# 4OR_1.net
KiCad netlist of a schematic drawn in EAGLE
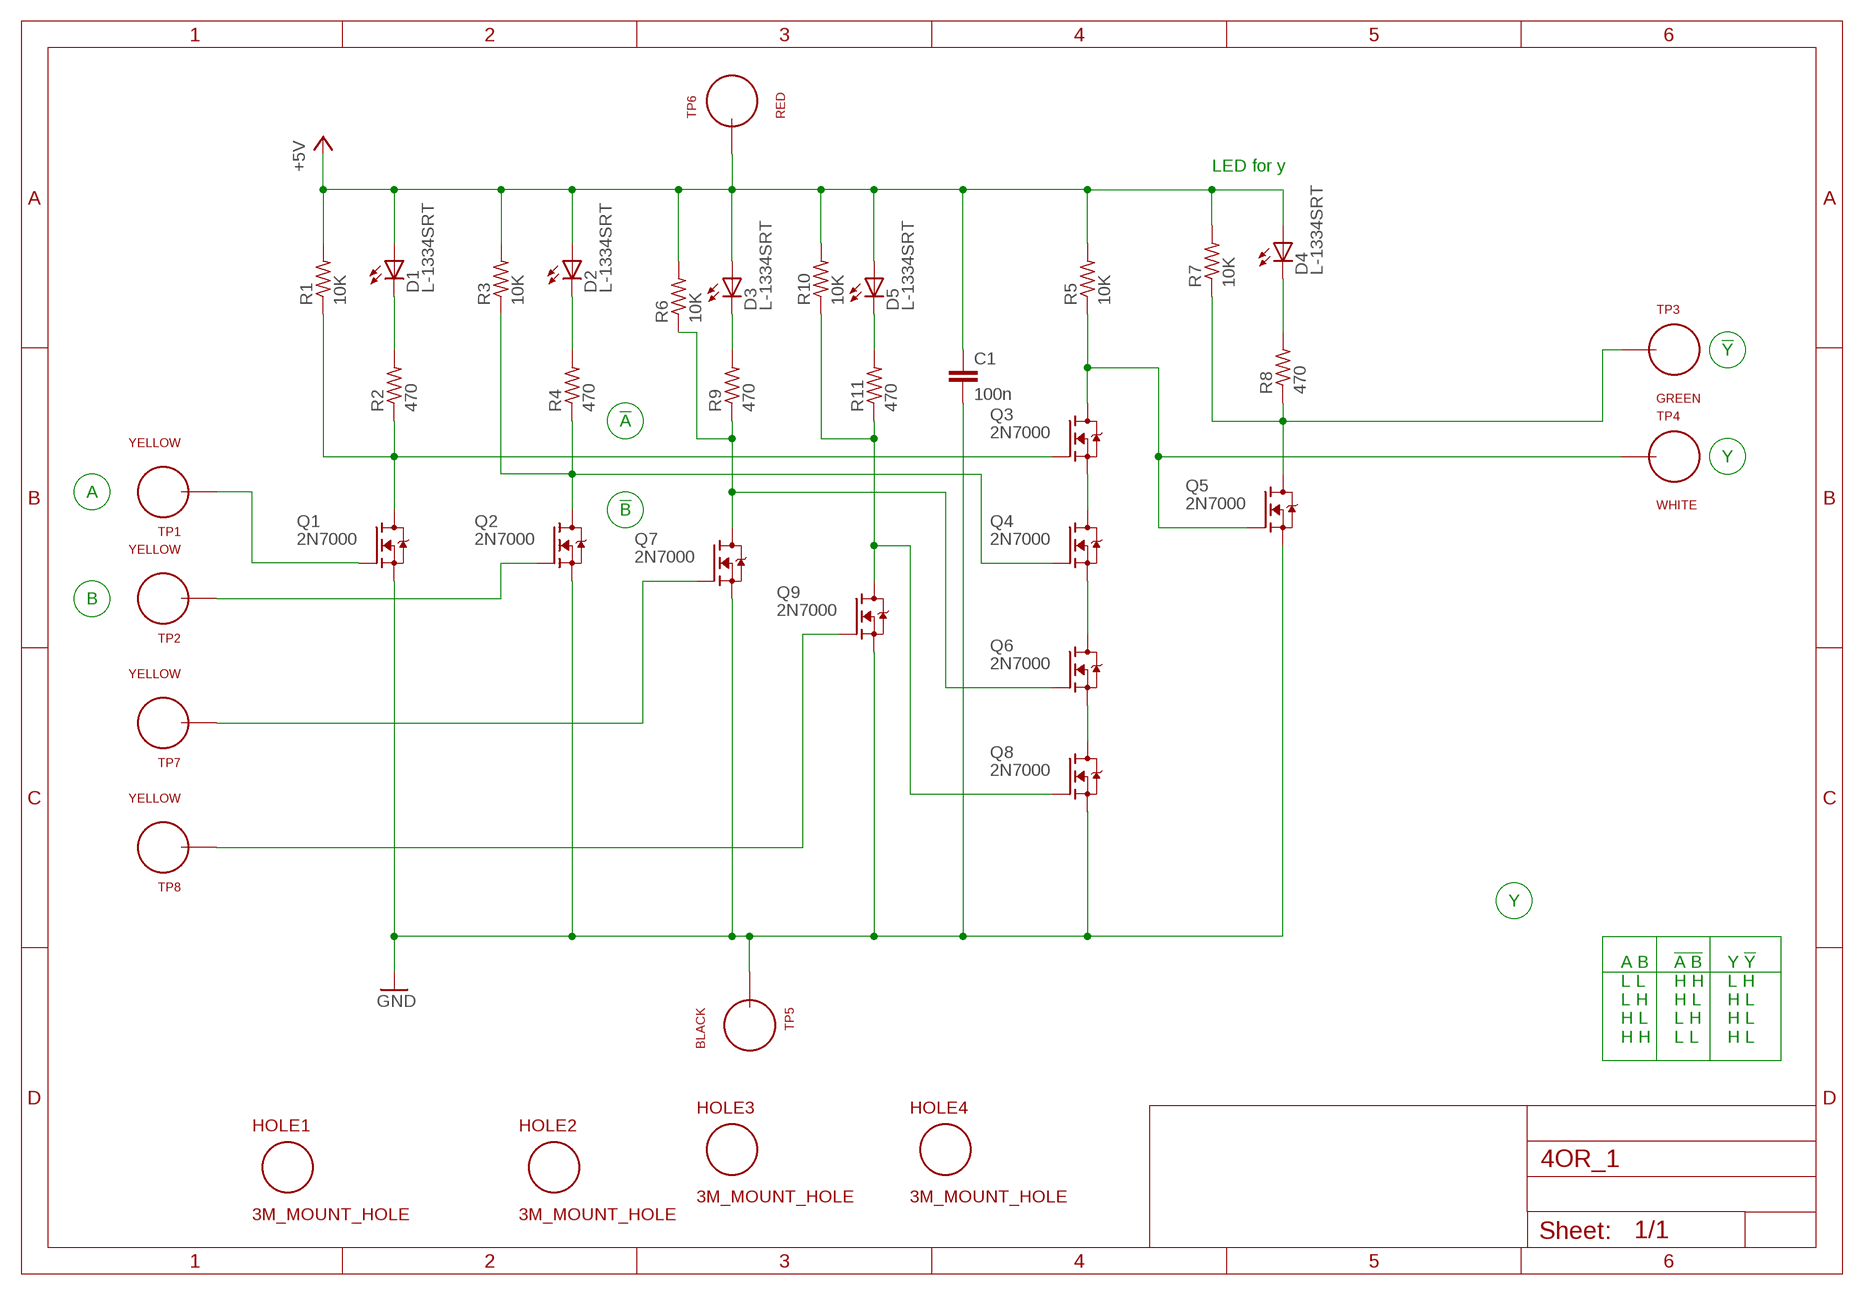
[diagram p0: schematic, sheet 1]

(export (version "E")
  (design (tool "Eeschema 10.0.6"))
  (components
    (comp (ref "C1")
      (value "100n")
      (footprint "eagle-import:CAP_P2INCH")
      (libsource (lib "eagle-import") (part "C_P2INCH"))
    )
    (comp (ref "D1")
      (value "L-1334SRT")
      (footprint "eagle-import:LED3MM")
      (libsource (lib "eagle-import") (part "L-1334SRT"))
    )
    (comp (ref "D2")
      (value "L-1334SRT")
      (footprint "eagle-import:LED3MM")
      (libsource (lib "eagle-import") (part "L-1334SRT"))
    )
    (comp (ref "D3")
      (value "L-1334SRT")
      (footprint "eagle-import:LED3MM")
      (libsource (lib "eagle-import") (part "L-1334SRT"))
    )
    (comp (ref "D4")
      (value "L-1334SRT")
      (footprint "eagle-import:LED3MM")
      (libsource (lib "eagle-import") (part "L-1334SRT"))
    )
    (comp (ref "D5")
      (value "L-1334SRT")
      (footprint "eagle-import:LED3MM")
      (libsource (lib "eagle-import") (part "L-1334SRT"))
    )
    (comp (ref "HOLE1")
      (value "3M_MOUNT_HOLE")
      (footprint "eagle-import:3M_HOLE")
      (libsource (lib "eagle-import") (part "3M_MOUNT_HOLE"))
    )
    (comp (ref "HOLE2")
      (value "3M_MOUNT_HOLE")
      (footprint "eagle-import:3M_HOLE")
      (libsource (lib "eagle-import") (part "3M_MOUNT_HOLE"))
    )
    (comp (ref "HOLE3")
      (value "3M_MOUNT_HOLE")
      (footprint "eagle-import:3M_HOLE")
      (libsource (lib "eagle-import") (part "3M_MOUNT_HOLE"))
    )
    (comp (ref "HOLE4")
      (value "3M_MOUNT_HOLE")
      (footprint "eagle-import:3M_HOLE")
      (libsource (lib "eagle-import") (part "3M_MOUNT_HOLE"))
    )
    (comp (ref "Q1")
      (value "2N7000")
      (footprint "eagle-import:TO92-DGS")
      (libsource (lib "eagle-import") (part "2N7000"))
    )
    (comp (ref "Q2")
      (value "2N7000")
      (footprint "eagle-import:TO92-DGS")
      (libsource (lib "eagle-import") (part "2N7000"))
    )
    (comp (ref "Q3")
      (value "2N7000")
      (footprint "eagle-import:TO92-DGS")
      (libsource (lib "eagle-import") (part "2N7000"))
    )
    (comp (ref "Q4")
      (value "2N7000")
      (footprint "eagle-import:TO92-DGS")
      (libsource (lib "eagle-import") (part "2N7000"))
    )
    (comp (ref "Q5")
      (value "2N7000")
      (footprint "eagle-import:TO92-DGS")
      (libsource (lib "eagle-import") (part "2N7000"))
    )
    (comp (ref "Q6")
      (value "2N7000")
      (footprint "eagle-import:TO92-DGS")
      (libsource (lib "eagle-import") (part "2N7000"))
    )
    (comp (ref "Q7")
      (value "2N7000")
      (footprint "eagle-import:TO92-DGS")
      (libsource (lib "eagle-import") (part "2N7000"))
    )
    (comp (ref "Q8")
      (value "2N7000")
      (footprint "eagle-import:TO92-DGS")
      (libsource (lib "eagle-import") (part "2N7000"))
    )
    (comp (ref "Q9")
      (value "2N7000")
      (footprint "eagle-import:TO92-DGS")
      (libsource (lib "eagle-import") (part "2N7000"))
    )
    (comp (ref "R1")
      (value "10K")
      (footprint "eagle-import:R_P2INCH")
      (libsource (lib "eagle-import") (part "R_P2INCH"))
    )
    (comp (ref "R2")
      (value "470")
      (footprint "eagle-import:R_P2INCH")
      (libsource (lib "eagle-import") (part "R_P2INCH"))
    )
    (comp (ref "R3")
      (value "10K")
      (footprint "eagle-import:R_P2INCH")
      (libsource (lib "eagle-import") (part "R_P2INCH"))
    )
    (comp (ref "R4")
      (value "470")
      (footprint "eagle-import:R_P2INCH")
      (libsource (lib "eagle-import") (part "R_P2INCH"))
    )
    (comp (ref "R5")
      (value "10K")
      (footprint "eagle-import:R_P2INCH")
      (libsource (lib "eagle-import") (part "R_P2INCH"))
    )
    (comp (ref "R6")
      (value "10K")
      (footprint "eagle-import:R_P2INCH")
      (libsource (lib "eagle-import") (part "R_P2INCH"))
    )
    (comp (ref "R7")
      (value "10K")
      (footprint "eagle-import:R_P2INCH")
      (libsource (lib "eagle-import") (part "R_P2INCH"))
    )
    (comp (ref "R8")
      (value "470")
      (footprint "eagle-import:R_P2INCH")
      (libsource (lib "eagle-import") (part "R_P2INCH"))
    )
    (comp (ref "R9")
      (value "470")
      (footprint "eagle-import:R_P2INCH")
      (libsource (lib "eagle-import") (part "R_P2INCH"))
    )
    (comp (ref "R10")
      (value "10K")
      (footprint "eagle-import:R_P2INCH")
      (libsource (lib "eagle-import") (part "R_P2INCH"))
    )
    (comp (ref "R11")
      (value "470")
      (footprint "eagle-import:R_P2INCH")
      (libsource (lib "eagle-import") (part "R_P2INCH"))
    )
    (comp (ref "TP1")
      (value "YELLOW")
      (footprint "eagle-import:TEST_LOOP")
      (libsource (lib "eagle-import") (part "TEST_LOOP"))
    )
    (comp (ref "TP2")
      (value "YELLOW")
      (footprint "eagle-import:TEST_LOOP")
      (libsource (lib "eagle-import") (part "TEST_LOOP"))
    )
    (comp (ref "TP3")
      (value "GREEN")
      (footprint "eagle-import:TEST_LOOP")
      (libsource (lib "eagle-import") (part "TEST_LOOP"))
    )
    (comp (ref "TP4")
      (value "WHITE")
      (footprint "eagle-import:TEST_LOOP")
      (libsource (lib "eagle-import") (part "TEST_LOOP"))
    )
    (comp (ref "TP5")
      (value "BLACK")
      (footprint "eagle-import:TEST_LOOP")
      (libsource (lib "eagle-import") (part "TEST_LOOP"))
    )
    (comp (ref "TP6")
      (value "RED")
      (footprint "eagle-import:TEST_LOOP")
      (libsource (lib "eagle-import") (part "TEST_LOOP"))
    )
    (comp (ref "TP7")
      (value "YELLOW")
      (footprint "eagle-import:TEST_LOOP")
      (libsource (lib "eagle-import") (part "TEST_LOOP"))
    )
    (comp (ref "TP8")
      (value "YELLOW")
      (footprint "eagle-import:TEST_LOOP")
      (libsource (lib "eagle-import") (part "TEST_LOOP"))
    )
  )
  (nets
    (net (code "1") (name "+5V") (class "Default")
      (node (ref "C1") (pin "1") (pinfunction "1_1") (pintype "passive"))
      (node (ref "D1") (pin "A") (pinfunction "A_A") (pintype "passive"))
      (node (ref "D2") (pin "A") (pinfunction "A_A") (pintype "passive"))
      (node (ref "D3") (pin "A") (pinfunction "A_A") (pintype "passive"))
      (node (ref "D4") (pin "A") (pinfunction "A_A") (pintype "passive"))
      (node (ref "D5") (pin "A") (pinfunction "A_A") (pintype "passive"))
      (node (ref "R1") (pin "2") (pinfunction "2_2") (pintype "passive"))
      (node (ref "R10") (pin "2") (pinfunction "2_2") (pintype "passive"))
      (node (ref "R3") (pin "2") (pinfunction "2_2") (pintype "passive"))
      (node (ref "R5") (pin "2") (pinfunction "2_2") (pintype "passive"))
      (node (ref "R6") (pin "2") (pinfunction "2_2") (pintype "passive"))
      (node (ref "R7") (pin "2") (pinfunction "2_2") (pintype "passive"))
      (node (ref "TP6") (pin "P$1") (pinfunction "P$1_P$1") (pintype "bidirectional"))
    )
    (net (code "2") (name "GND") (class "Default")
      (node (ref "C1") (pin "2") (pinfunction "2_2") (pintype "passive"))
      (node (ref "Q1") (pin "S") (pinfunction "S_S") (pintype "passive"))
      (node (ref "Q2") (pin "S") (pinfunction "S_S") (pintype "passive"))
      (node (ref "Q5") (pin "S") (pinfunction "S_S") (pintype "passive"))
      (node (ref "Q7") (pin "S") (pinfunction "S_S") (pintype "passive"))
      (node (ref "Q8") (pin "S") (pinfunction "S_S") (pintype "passive"))
      (node (ref "Q9") (pin "S") (pinfunction "S_S") (pintype "passive"))
      (node (ref "TP5") (pin "P$1") (pinfunction "P$1_P$1") (pintype "bidirectional"))
    )
    (net (code "3") (name "Net-(D1-C)") (class "Default")
      (node (ref "D1") (pin "K") (pinfunction "C_K") (pintype "passive"))
      (node (ref "R2") (pin "2") (pinfunction "2_2") (pintype "passive"))
    )
    (net (code "4") (name "Net-(D2-C)") (class "Default")
      (node (ref "D2") (pin "K") (pinfunction "C_K") (pintype "passive"))
      (node (ref "R4") (pin "2") (pinfunction "2_2") (pintype "passive"))
    )
    (net (code "5") (name "Net-(D3-C)") (class "Default")
      (node (ref "D3") (pin "K") (pinfunction "C_K") (pintype "passive"))
      (node (ref "R9") (pin "2") (pinfunction "2_2") (pintype "passive"))
    )
    (net (code "6") (name "Net-(D4-C)") (class "Default")
      (node (ref "D4") (pin "K") (pinfunction "C_K") (pintype "passive"))
      (node (ref "R8") (pin "2") (pinfunction "2_2") (pintype "passive"))
    )
    (net (code "7") (name "Net-(D5-C)") (class "Default")
      (node (ref "D5") (pin "K") (pinfunction "C_K") (pintype "passive"))
      (node (ref "R11") (pin "2") (pinfunction "2_2") (pintype "passive"))
    )
    (net (code "8") (name "Net-(Q1-PadD)") (class "Default")
      (node (ref "Q1") (pin "D") (pinfunction "D_D") (pintype "passive"))
      (node (ref "Q3") (pin "G") (pinfunction "G_G") (pintype "passive"))
      (node (ref "R1") (pin "1") (pinfunction "1_1") (pintype "passive"))
      (node (ref "R2") (pin "1") (pinfunction "1_1") (pintype "passive"))
    )
    (net (code "9") (name "Net-(Q1-PadG)") (class "Default")
      (node (ref "Q1") (pin "G") (pinfunction "G_G") (pintype "passive"))
      (node (ref "TP1") (pin "P$1") (pinfunction "P$1_P$1") (pintype "bidirectional"))
    )
    (net (code "10") (name "Net-(Q2-PadD)") (class "Default")
      (node (ref "Q2") (pin "D") (pinfunction "D_D") (pintype "passive"))
      (node (ref "Q4") (pin "G") (pinfunction "G_G") (pintype "passive"))
      (node (ref "R3") (pin "1") (pinfunction "1_1") (pintype "passive"))
      (node (ref "R4") (pin "1") (pinfunction "1_1") (pintype "passive"))
    )
    (net (code "11") (name "Net-(Q2-PadG)") (class "Default")
      (node (ref "Q2") (pin "G") (pinfunction "G_G") (pintype "passive"))
      (node (ref "TP2") (pin "P$1") (pinfunction "P$1_P$1") (pintype "bidirectional"))
    )
    (net (code "12") (name "Net-(Q3-PadD)") (class "Default")
      (node (ref "Q3") (pin "D") (pinfunction "D_D") (pintype "passive"))
      (node (ref "Q5") (pin "G") (pinfunction "G_G") (pintype "passive"))
      (node (ref "R5") (pin "1") (pinfunction "1_1") (pintype "passive"))
      (node (ref "TP4") (pin "P$1") (pinfunction "P$1_P$1") (pintype "bidirectional"))
    )
    (net (code "13") (name "Net-(Q3-PadS)") (class "Default")
      (node (ref "Q3") (pin "S") (pinfunction "S_S") (pintype "passive"))
      (node (ref "Q4") (pin "D") (pinfunction "D_D") (pintype "passive"))
    )
    (net (code "14") (name "Net-(Q4-PadS)") (class "Default")
      (node (ref "Q4") (pin "S") (pinfunction "S_S") (pintype "passive"))
      (node (ref "Q6") (pin "D") (pinfunction "D_D") (pintype "passive"))
    )
    (net (code "15") (name "Net-(Q5-PadD)") (class "Default")
      (node (ref "Q5") (pin "D") (pinfunction "D_D") (pintype "passive"))
      (node (ref "R7") (pin "1") (pinfunction "1_1") (pintype "passive"))
      (node (ref "R8") (pin "1") (pinfunction "1_1") (pintype "passive"))
      (node (ref "TP3") (pin "P$1") (pinfunction "P$1_P$1") (pintype "bidirectional"))
    )
    (net (code "16") (name "Net-(Q6-PadG)") (class "Default")
      (node (ref "Q6") (pin "G") (pinfunction "G_G") (pintype "passive"))
      (node (ref "Q7") (pin "D") (pinfunction "D_D") (pintype "passive"))
      (node (ref "R6") (pin "1") (pinfunction "1_1") (pintype "passive"))
      (node (ref "R9") (pin "1") (pinfunction "1_1") (pintype "passive"))
    )
    (net (code "17") (name "Net-(Q6-PadS)") (class "Default")
      (node (ref "Q6") (pin "S") (pinfunction "S_S") (pintype "passive"))
      (node (ref "Q8") (pin "D") (pinfunction "D_D") (pintype "passive"))
    )
    (net (code "18") (name "Net-(Q7-PadG)") (class "Default")
      (node (ref "Q7") (pin "G") (pinfunction "G_G") (pintype "passive"))
      (node (ref "TP7") (pin "P$1") (pinfunction "P$1_P$1") (pintype "bidirectional"))
    )
    (net (code "19") (name "Net-(Q8-PadG)") (class "Default")
      (node (ref "Q8") (pin "G") (pinfunction "G_G") (pintype "passive"))
      (node (ref "Q9") (pin "D") (pinfunction "D_D") (pintype "passive"))
      (node (ref "R10") (pin "1") (pinfunction "1_1") (pintype "passive"))
      (node (ref "R11") (pin "1") (pinfunction "1_1") (pintype "passive"))
    )
    (net (code "20") (name "Net-(Q9-PadG)") (class "Default")
      (node (ref "Q9") (pin "G") (pinfunction "G_G") (pintype "passive"))
      (node (ref "TP8") (pin "P$1") (pinfunction "P$1_P$1") (pintype "bidirectional"))
    )
  )
)
